# main.net
KiCad netlist of a schematic drawn in EAGLE
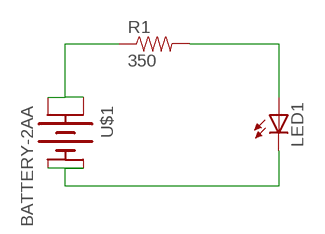
[diagram p0: schematic, sheet 1]

(export (version "E")
  (design (tool "Eeschema 10.0.6"))
  (components
    (comp (ref "LED1")
      (value "LED5MM")
      (footprint "eagle-import:LED5MM")
      (libsource (lib "eagle-import") (part "LED5MM"))
    )
    (comp (ref "R1")
      (value "350")
      (footprint "eagle-import:1206")
      (libsource (lib "eagle-import") (part "RESISTOR1206"))
    )
    (comp (ref "U$1")
      (value "BATTERY-2AA")
      (footprint "eagle-import:BATTERY-AA")
      (libsource (lib "eagle-import") (part "BATTERY-2AA"))
    )
  )
  (nets
    (net (code "1") (name "Net-(LED1-C)") (class "Default")
      (node (ref "LED1") (pin "K") (pinfunction "C_K") (pintype "passive"))
      (node (ref "U$1") (pin "GND@1") (pinfunction "-1_GND@1") (pintype "power_in"))
      (node (ref "U$1") (pin "GND@2") (pinfunction "-2_GND@2") (pintype "power_in"))
    )
    (net (code "2") (name "Net-(LED1-PadA)") (class "Default")
      (node (ref "LED1") (pin "A") (pinfunction "A_A") (pintype "passive"))
      (node (ref "R1") (pin "2") (pinfunction "2_2") (pintype "passive"))
    )
    (net (code "3") (name "Net-(U$1-+1)") (class "Default")
      (node (ref "R1") (pin "1") (pinfunction "1_1") (pintype "passive"))
      (node (ref "U$1") (pin "PWR@1") (pinfunction "+1_PWR@1") (pintype "power_in"))
      (node (ref "U$1") (pin "PWR@2") (pinfunction "+2_PWR@2") (pintype "power_in"))
    )
  )
)
